# InverterAmp.net
KiCad netlist of a schematic drawn in Altium Designer
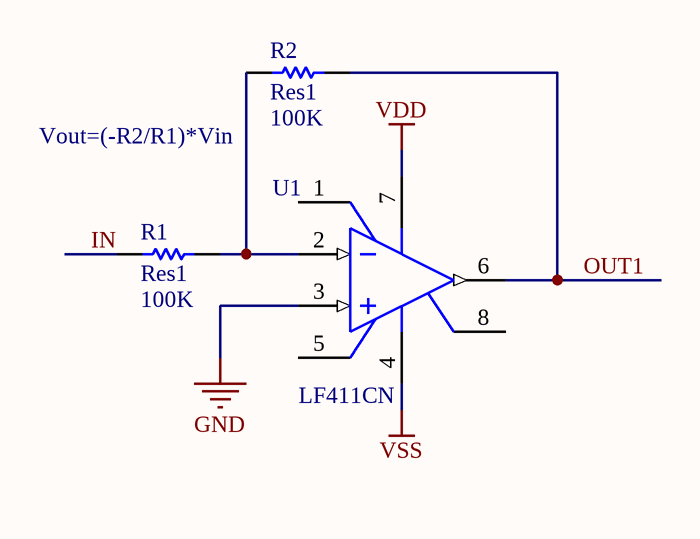
[diagram p0: InverterAmp.SchDoc]

(export (version "E")
  (design (tool "Eeschema 10.0.6"))
  (components
    (comp (ref "R1")
      (value "Res1")
      (footprint "AXIAL-0.3")
      (description "Resistor")
      (fields (field (name "ALTIUM_VALUE") "100K") (field (name "PUBLISHER") "Altium Limited"))
      (libsource (lib "Miscellaneous Devices") (part "Res1"))
    )
    (comp (ref "R2")
      (value "Res1")
      (footprint "AXIAL-0.3")
      (description "Resistor")
      (fields (field (name "ALTIUM_VALUE") "100K") (field (name "PUBLISHER") "Altium Limited"))
      (libsource (lib "Miscellaneous Devices") (part "Res1"))
    )
    (comp (ref "U1")
      (value "LF411CN")
      (footprint "N08E")
      (description "Low Offset, Low Drift JFET Input Operational Amplifier, 8-pin MDIP")
      (fields
        (field (name "MANUFACTURER") "National Semiconductor")
        (field (name "PUBLISHER") "Altium Limited")
      )
      (libsource (lib "NSC Amplifier") (part "LF411CN"))
    )
  )
  (nets
    (net (code "1") (name "/IN") (class "Default")
      (node (ref "R1") (pin "2") (pinfunction "2_2") (pintype "passive"))
    )
    (net (code "2") (name "/OUT1") (class "Default")
      (node (ref "R2") (pin "1") (pinfunction "1_1") (pintype "passive"))
      (node (ref "U1") (pin "6") (pinfunction "OUT_6") (pintype "output"))
    )
    (net (code "3") (name "GND") (class "Default")
      (node (ref "U1") (pin "3") (pinfunction "IN+_3") (pintype "input"))
    )
    (net (code "4") (name "Net-(U1-IN-)") (class "Default")
      (node (ref "R1") (pin "1") (pinfunction "1_1") (pintype "passive"))
      (node (ref "R2") (pin "2") (pinfunction "2_2") (pintype "passive"))
      (node (ref "U1") (pin "2") (pinfunction "IN-_2") (pintype "input"))
    )
    (net (code "5") (name "VDD") (class "Default")
      (node (ref "U1") (pin "7") (pinfunction "V+_7") (pintype "power_in"))
    )
    (net (code "6") (name "VSS") (class "Default")
      (node (ref "U1") (pin "4") (pinfunction "V-_4") (pintype "power_in"))
    )
    (net (code "7") (name "unconnected-(U1-BAL-Pad1)") (class "Default")
      (node (ref "U1") (pin "1") (pinfunction "BAL_1") (pintype "passive"))
    )
    (net (code "8") (name "unconnected-(U1-BAL-Pad5)") (class "Default")
      (node (ref "U1") (pin "5") (pinfunction "BAL_5") (pintype "passive"))
    )
    (net (code "9") (name "unconnected-(U1-NC-Pad8)") (class "Default")
      (node (ref "U1") (pin "8") (pinfunction "NC_8") (pintype "passive"))
    )
  )
)
